# Buzzer.net
KiCad netlist of a schematic drawn in Altium Designer
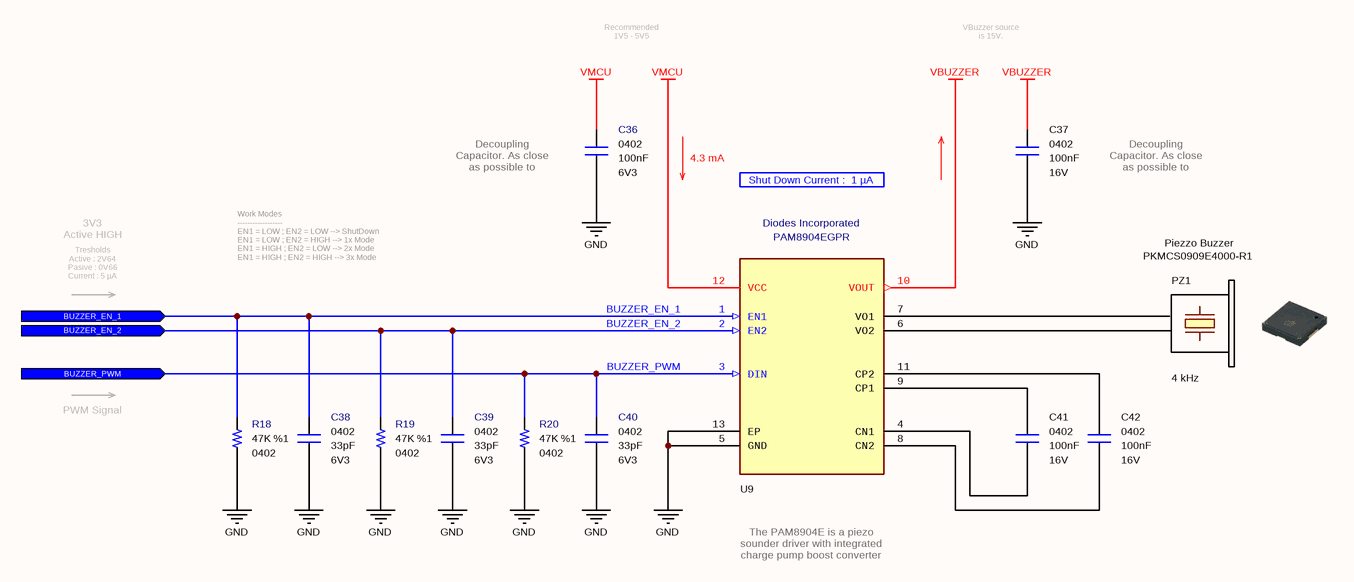
[diagram p0: Buzzer.SchDoc]

(export (version "E")
  (design (tool "Eeschema 10.0.6"))
  (components
    (comp (ref "C36")
      (value "100nF")
      (footprint "CAPACITOR_0402")
      (description "Capacitor - 100nF [0402-6V3] (Ceramic)")
      (fields
        (field (name "TOLERANCE") "%10")
        (field (name "CASE") "0402")
        (field (name "VOLTAGE") "6V3")
        (field (name "MANUFACTURER PART NUMBER") "04026D104KAT4A")
      )
      (libsource (lib "Ovoo_Library") (part "Capacitor - 100nF [0402-6V3]"))
    )
    (comp (ref "C37")
      (value "100nF")
      (footprint "CAPACITOR_0402")
      (description "Capacitor - 100nF [0402] (Ceramic)")
      (fields
        (field (name "MANUFACTURER PART NUMBER") "0402YC104KAT2A")
        (field (name "MOUSER PART NUMBER") "581-0402YC104KAT2A")
        (field (name "CASE") "0402")
        (field (name "VOLTAGE") "16V")
      )
      (libsource (lib "Ovoo_Library") (part "Capacitor - 100nF [0402-16V]"))
    )
    (comp (ref "C38")
      (value "33pF")
      (footprint "CAPACITOR_0402")
      (description "Capacitor - 33pF [0402] (Ceramic)")
      (fields
        (field (name "TOLERANCE") "10%")
        (field (name "CASE") "0402")
        (field (name "VOLTAGE") "6V3")
        (field (name "MANUFACTURER PART NUMBER") "C0402C330J9RACAUTO")
      )
      (libsource (lib "Ovoo_Library") (part "Capacitor - 33pF [0402-6V3]"))
    )
    (comp (ref "C39")
      (value "33pF")
      (footprint "CAPACITOR_0402")
      (description "Capacitor - 33pF [0402] (Ceramic)")
      (fields
        (field (name "TOLERANCE") "10%")
        (field (name "CASE") "0402")
        (field (name "VOLTAGE") "6V3")
        (field (name "MANUFACTURER PART NUMBER") "C0402C330J9RACAUTO")
      )
      (libsource (lib "Ovoo_Library") (part "Capacitor - 33pF [0402-6V3]"))
    )
    (comp (ref "C40")
      (value "33pF")
      (footprint "CAPACITOR_0402")
      (description "Capacitor - 33pF [0402] (Ceramic)")
      (fields
        (field (name "TOLERANCE") "10%")
        (field (name "CASE") "0402")
        (field (name "VOLTAGE") "6V3")
        (field (name "MANUFACTURER PART NUMBER") "C0402C330J9RACAUTO")
      )
      (libsource (lib "Ovoo_Library") (part "Capacitor - 33pF [0402-6V3]"))
    )
    (comp (ref "C41")
      (value "100nF")
      (footprint "CAPACITOR_0402")
      (description "Capacitor - 100nF [0402] (Ceramic)")
      (fields
        (field (name "MANUFACTURER PART NUMBER") "0402YC104KAT2A")
        (field (name "MOUSER PART NUMBER") "581-0402YC104KAT2A")
        (field (name "CASE") "0402")
        (field (name "VOLTAGE") "16V")
      )
      (libsource (lib "Ovoo_Library") (part "Capacitor - 100nF [0402-16V]"))
    )
    (comp (ref "C42")
      (value "100nF")
      (footprint "CAPACITOR_0402")
      (description "Capacitor - 100nF [0402] (Ceramic)")
      (fields
        (field (name "MANUFACTURER PART NUMBER") "0402YC104KAT2A")
        (field (name "MOUSER PART NUMBER") "581-0402YC104KAT2A")
        (field (name "CASE") "0402")
        (field (name "VOLTAGE") "16V")
      )
      (libsource (lib "Ovoo_Library") (part "Capacitor - 100nF [0402-16V]"))
    )
    (comp (ref "PZ1")
      (value "Piezo Buzzers & Audio Indicators")
      (footprint "Murata Piezzo Buzzer")
      (description "Piezo Buzzers & Audio Indicators Piezo Buzzer 9x9mm 4KHz 1.9mm Thickness")
      (fields
        (field (name "FREQUENCY") "4 kHz")
        (field (name "MANUFACTURER PART NUMBER") "PKMCS0909E4000-R1")
        (field (name "DEVICE TYPE") "Piezzo Buzzer")
      )
      (libsource (lib "Ovoo_Library") (part "Buzzer - PKMCS0909E4000-R1"))
    )
    (comp (ref "R18")
      (value "47K")
      (footprint "RESISTOR_0402")
      (description "Thick Film Resistors - SMD 1/16 W 47 Kohms 1%")
      (fields
        (field (name "TOLERANCE") "%1")
        (field (name "CASE") "0402")
        (field (name "MANUFACTURER PART NUMBER") "CRCW040247K0FKED")
        (field (name "Comment") "47K - 0402 - %1 - 1/16W")
      )
      (libsource (lib "Ovoo_Library") (part "Resistor - 47K"))
    )
    (comp (ref "R19")
      (value "47K")
      (footprint "RESISTOR_0402")
      (description "Thick Film Resistors - SMD 1/16 W 47 Kohms 1%")
      (fields
        (field (name "TOLERANCE") "%1")
        (field (name "CASE") "0402")
        (field (name "MANUFACTURER PART NUMBER") "CRCW040247K0FKED")
        (field (name "Comment") "47K - 0402 - %1 - 1/16W")
      )
      (libsource (lib "Ovoo_Library") (part "Resistor - 47K"))
    )
    (comp (ref "R20")
      (value "47K")
      (footprint "RESISTOR_0402")
      (description "Thick Film Resistors - SMD 1/16 W 47 Kohms 1%")
      (fields
        (field (name "TOLERANCE") "%1")
        (field (name "CASE") "0402")
        (field (name "MANUFACTURER PART NUMBER") "CRCW040247K0FKED")
        (field (name "Comment") "47K - 0402 - %1 - 1/16W")
      )
      (libsource (lib "Ovoo_Library") (part "Resistor - 47K"))
    )
    (comp (ref "U9")
      (value "Audio Amplifiers")
      (footprint "QFN2020-12")
      (description "Audio Amplifiers Audio High Volt")
      (fields
        (field (name "MANUFACTURER NAME") "Diodes Incorporated")
        (field (name "MANUFACTURER PART NUMBER") "PAM8904EGPR")
      )
      (libsource (lib "Ovoo_Library") (part "IC - PAM8904EGPR"))
    )
  )
  (nets
    (net (code "1") (name "/BUZZER_EN_1") (class "Default")
      (node (ref "C38") (pin "2") (pinfunction "2_2") (pintype "passive"))
      (node (ref "R18") (pin "2") (pinfunction "2_2") (pintype "passive"))
      (node (ref "U9") (pin "1") (pinfunction "EN1_1") (pintype "input"))
    )
    (net (code "2") (name "/BUZZER_EN_2") (class "Default")
      (node (ref "C39") (pin "2") (pinfunction "2_2") (pintype "passive"))
      (node (ref "R19") (pin "2") (pinfunction "2_2") (pintype "passive"))
      (node (ref "U9") (pin "2") (pinfunction "EN2_2") (pintype "input"))
    )
    (net (code "3") (name "/BUZZER_PWM") (class "Default")
      (node (ref "C40") (pin "2") (pinfunction "2_2") (pintype "passive"))
      (node (ref "R20") (pin "2") (pinfunction "2_2") (pintype "passive"))
      (node (ref "U9") (pin "3") (pinfunction "DIN_3") (pintype "input"))
    )
    (net (code "4") (name "GND") (class "Default")
      (node (ref "C36") (pin "1") (pinfunction "1_1") (pintype "passive"))
      (node (ref "C37") (pin "1") (pinfunction "1_1") (pintype "passive"))
      (node (ref "C38") (pin "1") (pinfunction "1_1") (pintype "passive"))
      (node (ref "C39") (pin "1") (pinfunction "1_1") (pintype "passive"))
      (node (ref "C40") (pin "1") (pinfunction "1_1") (pintype "passive"))
      (node (ref "R18") (pin "1") (pinfunction "1_1") (pintype "passive"))
      (node (ref "R19") (pin "1") (pinfunction "1_1") (pintype "passive"))
      (node (ref "R20") (pin "1") (pinfunction "1_1") (pintype "passive"))
      (node (ref "U9") (pin "13") (pinfunction "EP_13") (pintype "passive"))
      (node (ref "U9") (pin "5") (pinfunction "GND_5") (pintype "passive"))
    )
    (net (code "5") (name "Net-(PZ1-+)") (class "Default")
      (node (ref "PZ1") (pin "1") (pinfunction "+_1") (pintype "passive"))
      (node (ref "U9") (pin "7") (pinfunction "VO1_7") (pintype "power_in"))
    )
    (net (code "6") (name "Net-(PZ1--)") (class "Default")
      (node (ref "PZ1") (pin "2") (pinfunction "-_2") (pintype "passive"))
      (node (ref "U9") (pin "6") (pinfunction "VO2_6") (pintype "passive"))
    )
    (net (code "7") (name "Net-(U9-CN1)") (class "Default")
      (node (ref "C41") (pin "1") (pinfunction "1_1") (pintype "passive"))
      (node (ref "U9") (pin "4") (pinfunction "CN1_4") (pintype "passive"))
    )
    (net (code "8") (name "Net-(U9-CN2)") (class "Default")
      (node (ref "C42") (pin "1") (pinfunction "1_1") (pintype "passive"))
      (node (ref "U9") (pin "8") (pinfunction "CN2_8") (pintype "passive"))
    )
    (net (code "9") (name "Net-(U9-CP1)") (class "Default")
      (node (ref "C41") (pin "2") (pinfunction "2_2") (pintype "passive"))
      (node (ref "U9") (pin "9") (pinfunction "CP1_9") (pintype "passive"))
    )
    (net (code "10") (name "Net-(U9-CP2)") (class "Default")
      (node (ref "C42") (pin "2") (pinfunction "2_2") (pintype "passive"))
      (node (ref "U9") (pin "11") (pinfunction "CP2_11") (pintype "passive"))
    )
    (net (code "11") (name "VBUZZER") (class "Default")
      (node (ref "C37") (pin "2") (pinfunction "2_2") (pintype "passive"))
      (node (ref "U9") (pin "10") (pinfunction "VOUT_10") (pintype "output"))
    )
    (net (code "12") (name "VMCU") (class "Default")
      (node (ref "C36") (pin "2") (pinfunction "2_2") (pintype "passive"))
      (node (ref "U9") (pin "12") (pinfunction "VCC_12") (pintype "power_in"))
    )
  )
)
